# dual_encoder_shield_revC.net
KiCad netlist of a schematic drawn in EAGLE
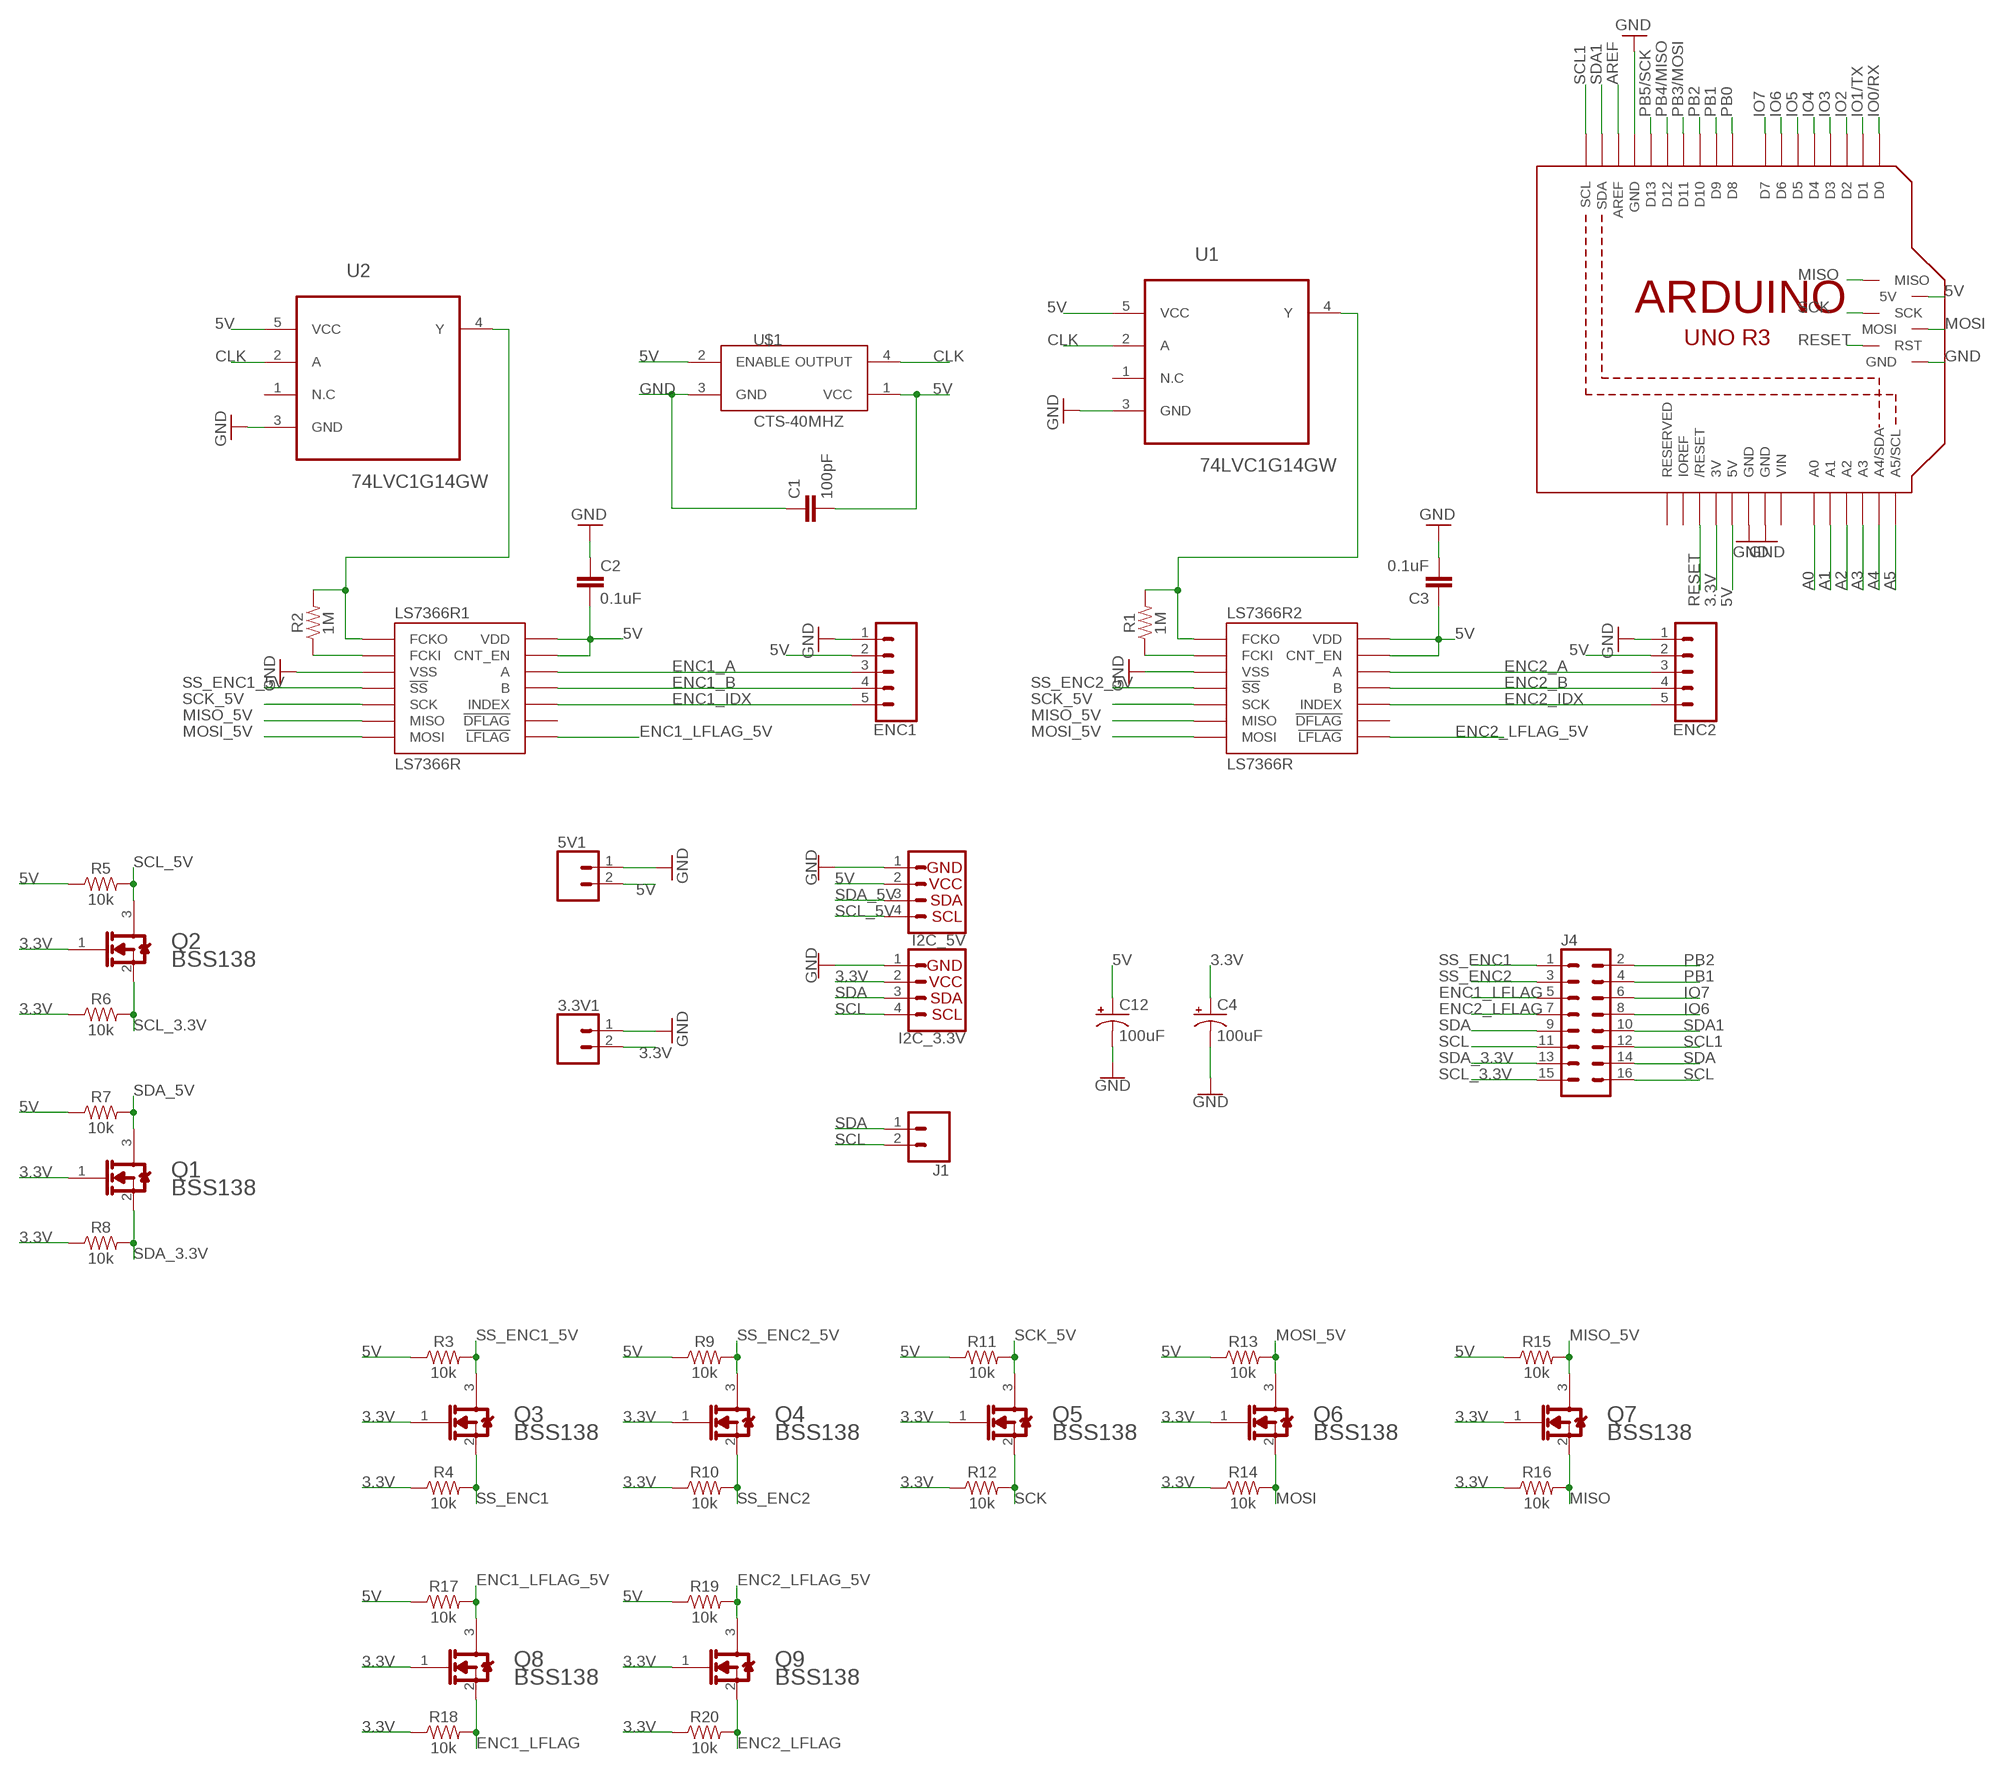
[diagram p0: schematic, sheet 1]

(export (version "E")
  (design (tool "Eeschema 10.0.6"))
  (components
    (comp (ref "3.3V1")
      (value "CONN_02-JST-2MM-SMT")
      (footprint "eagle-import:JST-2-SMD")
      (libsource (lib "eagle-import") (part "CONN_02-JST-2MM-SMT"))
    )
    (comp (ref "5V1")
      (value "CONN_02-JST-2MM-SMT")
      (footprint "eagle-import:JST-2-SMD")
      (libsource (lib "eagle-import") (part "CONN_02-JST-2MM-SMT"))
    )
    (comp (ref "C1")
      (value "100pF")
      (footprint "eagle-import:0603")
      (libsource (lib "eagle-import") (part "100PF-0603-50V-5%"))
    )
    (comp (ref "C2")
      (value "0.1uF")
      (footprint "eagle-import:0603")
      (libsource (lib "eagle-import") (part "0.1UF-0603-25V-5%"))
    )
    (comp (ref "C3")
      (value "0.1uF")
      (footprint "eagle-import:0603")
      (libsource (lib "eagle-import") (part "0.1UF-0603-25V-5%"))
    )
    (comp (ref "C4")
      (value "100uF")
      (footprint "eagle-import:PANASONIC_D")
      (libsource (lib "eagle-import") (part "100UF-POLAR-25V-20%(ELEC)"))
    )
    (comp (ref "C12")
      (value "100uF")
      (footprint "eagle-import:PANASONIC_D")
      (libsource (lib "eagle-import") (part "100UF-POLAR-25V-20%(ELEC)"))
    )
    (comp (ref "ENC1")
      (value "CONN_05")
      (footprint "eagle-import:1X05")
      (libsource (lib "eagle-import") (part "CONN_05"))
    )
    (comp (ref "ENC2")
      (value "CONN_05")
      (footprint "eagle-import:1X05")
      (libsource (lib "eagle-import") (part "CONN_05"))
    )
    (comp (ref "I2C_3.3V")
      (value "QWIIC_CONNECTORJS-1MM")
      (footprint "eagle-import:JST04_1MM_RA")
      (libsource (lib "eagle-import") (part "QWIIC_CONNECTORJS-1MM"))
    )
    (comp (ref "I2C_5V")
      (value "QWIIC_CONNECTORJS-1MM")
      (footprint "eagle-import:JST04_1MM_RA")
      (libsource (lib "eagle-import") (part "QWIIC_CONNECTORJS-1MM"))
    )
    (comp (ref "J1")
      (value "CONN_02")
      (footprint "eagle-import:1X02")
      (libsource (lib "eagle-import") (part "CONN_02"))
    )
    (comp (ref "J4")
      (value "CONN_08X2")
      (footprint "eagle-import:2X8")
      (libsource (lib "eagle-import") (part "CONN_08X2"))
    )
    (comp (ref "LS7366R1")
      (value "LS7366R")
      (footprint "eagle-import:SOIC14")
      (fields (field (name "MF") "LSI"))
      (libsource (lib "eagle-import") (part "LS7366R"))
    )
    (comp (ref "LS7366R2")
      (value "LS7366R")
      (footprint "eagle-import:SOIC14")
      (fields (field (name "MF") "LSI"))
      (libsource (lib "eagle-import") (part "LS7366R"))
    )
    (comp (ref "M1")
      (value "ARDUINO_R3_ICSP")
      (footprint "eagle-import:ARDUINOR3_ICSP")
      (libsource (lib "eagle-import") (part "ARDUINO_R3_ICSP"))
    )
    (comp (ref "Q1")
      (value "ON_SEMI_BSS138ON_SEMI_BSS138_0_0")
      (footprint "eagle-import:ON_SEMI_BSS138_0")
      (fields
        (field (name "DIGIKEY_PART_NUMBER") "BSS138CT-ND")
        (field (name "MF") "ON Semi")
        (field (name "MOUSER_PART_NUMBER") "512-BSS138")
      )
      (libsource (lib "eagle-import") (part "ON_SEMI_BSS138ON_SEMI_BSS138_0_0"))
    )
    (comp (ref "Q2")
      (value "ON_SEMI_BSS138ON_SEMI_BSS138_0_0")
      (footprint "eagle-import:ON_SEMI_BSS138_0")
      (fields
        (field (name "DIGIKEY_PART_NUMBER") "BSS138CT-ND")
        (field (name "MF") "ON Semi")
        (field (name "MOUSER_PART_NUMBER") "512-BSS138")
      )
      (libsource (lib "eagle-import") (part "ON_SEMI_BSS138ON_SEMI_BSS138_0_0"))
    )
    (comp (ref "Q3")
      (value "ON_SEMI_BSS138ON_SEMI_BSS138_0_0")
      (footprint "eagle-import:ON_SEMI_BSS138_0")
      (fields
        (field (name "DIGIKEY_PART_NUMBER") "BSS138CT-ND")
        (field (name "MF") "ON Semi")
        (field (name "MOUSER_PART_NUMBER") "512-BSS138")
      )
      (libsource (lib "eagle-import") (part "ON_SEMI_BSS138ON_SEMI_BSS138_0_0"))
    )
    (comp (ref "Q4")
      (value "ON_SEMI_BSS138ON_SEMI_BSS138_0_0")
      (footprint "eagle-import:ON_SEMI_BSS138_0")
      (fields
        (field (name "DIGIKEY_PART_NUMBER") "BSS138CT-ND")
        (field (name "MF") "ON Semi")
        (field (name "MOUSER_PART_NUMBER") "512-BSS138")
      )
      (libsource (lib "eagle-import") (part "ON_SEMI_BSS138ON_SEMI_BSS138_0_0"))
    )
    (comp (ref "Q5")
      (value "ON_SEMI_BSS138ON_SEMI_BSS138_0_0")
      (footprint "eagle-import:ON_SEMI_BSS138_0")
      (fields
        (field (name "DIGIKEY_PART_NUMBER") "BSS138CT-ND")
        (field (name "MF") "ON Semi")
        (field (name "MOUSER_PART_NUMBER") "512-BSS138")
      )
      (libsource (lib "eagle-import") (part "ON_SEMI_BSS138ON_SEMI_BSS138_0_0"))
    )
    (comp (ref "Q6")
      (value "ON_SEMI_BSS138ON_SEMI_BSS138_0_0")
      (footprint "eagle-import:ON_SEMI_BSS138_0")
      (fields
        (field (name "DIGIKEY_PART_NUMBER") "BSS138CT-ND")
        (field (name "MF") "ON Semi")
        (field (name "MOUSER_PART_NUMBER") "512-BSS138")
      )
      (libsource (lib "eagle-import") (part "ON_SEMI_BSS138ON_SEMI_BSS138_0_0"))
    )
    (comp (ref "Q7")
      (value "ON_SEMI_BSS138ON_SEMI_BSS138_0_0")
      (footprint "eagle-import:ON_SEMI_BSS138_0")
      (fields
        (field (name "DIGIKEY_PART_NUMBER") "BSS138CT-ND")
        (field (name "MF") "ON Semi")
        (field (name "MOUSER_PART_NUMBER") "512-BSS138")
      )
      (libsource (lib "eagle-import") (part "ON_SEMI_BSS138ON_SEMI_BSS138_0_0"))
    )
    (comp (ref "Q8")
      (value "ON_SEMI_BSS138ON_SEMI_BSS138_0_0")
      (footprint "eagle-import:ON_SEMI_BSS138_0")
      (fields
        (field (name "DIGIKEY_PART_NUMBER") "BSS138CT-ND")
        (field (name "MF") "ON Semi")
        (field (name "MOUSER_PART_NUMBER") "512-BSS138")
      )
      (libsource (lib "eagle-import") (part "ON_SEMI_BSS138ON_SEMI_BSS138_0_0"))
    )
    (comp (ref "Q9")
      (value "ON_SEMI_BSS138ON_SEMI_BSS138_0_0")
      (footprint "eagle-import:ON_SEMI_BSS138_0")
      (fields
        (field (name "DIGIKEY_PART_NUMBER") "BSS138CT-ND")
        (field (name "MF") "ON Semi")
        (field (name "MOUSER_PART_NUMBER") "512-BSS138")
      )
      (libsource (lib "eagle-import") (part "ON_SEMI_BSS138ON_SEMI_BSS138_0_0"))
    )
    (comp (ref "R1")
      (value "1M")
      (footprint "eagle-import:0603")
      (libsource (lib "eagle-import") (part "1MOHM-0603-1/4W-5%"))
    )
    (comp (ref "R2")
      (value "1M")
      (footprint "eagle-import:0603")
      (libsource (lib "eagle-import") (part "1MOHM-0603-1/4W-5%"))
    )
    (comp (ref "R3")
      (value "10k")
      (footprint "eagle-import:0603")
      (libsource (lib "eagle-import") (part "10KOHM-0603-1/10W-1%"))
    )
    (comp (ref "R4")
      (value "10k")
      (footprint "eagle-import:0603")
      (libsource (lib "eagle-import") (part "10KOHM-0603-1/10W-1%"))
    )
    (comp (ref "R5")
      (value "10k")
      (footprint "eagle-import:0603")
      (libsource (lib "eagle-import") (part "10KOHM-0603-1/10W-1%"))
    )
    (comp (ref "R6")
      (value "10k")
      (footprint "eagle-import:0603")
      (libsource (lib "eagle-import") (part "10KOHM-0603-1/10W-1%"))
    )
    (comp (ref "R7")
      (value "10k")
      (footprint "eagle-import:0603")
      (libsource (lib "eagle-import") (part "10KOHM-0603-1/10W-1%"))
    )
    (comp (ref "R8")
      (value "10k")
      (footprint "eagle-import:0603")
      (libsource (lib "eagle-import") (part "10KOHM-0603-1/10W-1%"))
    )
    (comp (ref "R9")
      (value "10k")
      (footprint "eagle-import:0603")
      (libsource (lib "eagle-import") (part "10KOHM-0603-1/10W-1%"))
    )
    (comp (ref "R10")
      (value "10k")
      (footprint "eagle-import:0603")
      (libsource (lib "eagle-import") (part "10KOHM-0603-1/10W-1%"))
    )
    (comp (ref "R11")
      (value "10k")
      (footprint "eagle-import:0603")
      (libsource (lib "eagle-import") (part "10KOHM-0603-1/10W-1%"))
    )
    (comp (ref "R12")
      (value "10k")
      (footprint "eagle-import:0603")
      (libsource (lib "eagle-import") (part "10KOHM-0603-1/10W-1%"))
    )
    (comp (ref "R13")
      (value "10k")
      (footprint "eagle-import:0603")
      (libsource (lib "eagle-import") (part "10KOHM-0603-1/10W-1%"))
    )
    (comp (ref "R14")
      (value "10k")
      (footprint "eagle-import:0603")
      (libsource (lib "eagle-import") (part "10KOHM-0603-1/10W-1%"))
    )
    (comp (ref "R15")
      (value "10k")
      (footprint "eagle-import:0603")
      (libsource (lib "eagle-import") (part "10KOHM-0603-1/10W-1%"))
    )
    (comp (ref "R16")
      (value "10k")
      (footprint "eagle-import:0603")
      (libsource (lib "eagle-import") (part "10KOHM-0603-1/10W-1%"))
    )
    (comp (ref "R17")
      (value "10k")
      (footprint "eagle-import:0603")
      (libsource (lib "eagle-import") (part "10KOHM-0603-1/10W-1%"))
    )
    (comp (ref "R18")
      (value "10k")
      (footprint "eagle-import:0603")
      (libsource (lib "eagle-import") (part "10KOHM-0603-1/10W-1%"))
    )
    (comp (ref "R19")
      (value "10k")
      (footprint "eagle-import:0603")
      (libsource (lib "eagle-import") (part "10KOHM-0603-1/10W-1%"))
    )
    (comp (ref "R20")
      (value "10k")
      (footprint "eagle-import:0603")
      (libsource (lib "eagle-import") (part "10KOHM-0603-1/10W-1%"))
    )
    (comp (ref "U$1")
      (value "CTS-40MHZ")
      (footprint "eagle-import:SOIC254P1016X440-4N")
      (libsource (lib "eagle-import") (part "CTS-40MHZ"))
    )
    (comp (ref "U1")
      (value "74LVC1G14GW")
      (footprint "eagle-import:SOT65P210X110-5N")
      (fields (field (name "MF") "NXP Semiconductors"))
      (libsource (lib "eagle-import") (part "74LVC1G14GW"))
    )
    (comp (ref "U2")
      (value "74LVC1G14GW")
      (footprint "eagle-import:SOT65P210X110-5N")
      (fields (field (name "MF") "NXP Semiconductors"))
      (libsource (lib "eagle-import") (part "74LVC1G14GW"))
    )
  )
  (nets
    (net (code "1") (name "/3.3V") (class "Default")
      (node (ref "3.3V1") (pin "2") (pinfunction "1_2") (pintype "passive"))
      (node (ref "C4") (pin "+") (pinfunction "+_+") (pintype "passive"))
      (node (ref "I2C_3.3V") (pin "2") (pinfunction "2_2") (pintype "power_in"))
      (node (ref "M1") (pin "3V") (pinfunction "3V_3V") (pintype "power_in"))
      (node (ref "Q1") (pin "1") (pinfunction "G_1") (pintype "bidirectional"))
      (node (ref "Q2") (pin "1") (pinfunction "G_1") (pintype "bidirectional"))
      (node (ref "Q3") (pin "1") (pinfunction "G_1") (pintype "bidirectional"))
      (node (ref "Q4") (pin "1") (pinfunction "G_1") (pintype "bidirectional"))
      (node (ref "Q5") (pin "1") (pinfunction "G_1") (pintype "bidirectional"))
      (node (ref "Q6") (pin "1") (pinfunction "G_1") (pintype "bidirectional"))
      (node (ref "Q7") (pin "1") (pinfunction "G_1") (pintype "bidirectional"))
      (node (ref "Q8") (pin "1") (pinfunction "G_1") (pintype "bidirectional"))
      (node (ref "Q9") (pin "1") (pinfunction "G_1") (pintype "bidirectional"))
      (node (ref "R10") (pin "1") (pinfunction "1_1") (pintype "passive"))
      (node (ref "R12") (pin "1") (pinfunction "1_1") (pintype "passive"))
      (node (ref "R14") (pin "1") (pinfunction "1_1") (pintype "passive"))
      (node (ref "R16") (pin "1") (pinfunction "1_1") (pintype "passive"))
      (node (ref "R18") (pin "1") (pinfunction "1_1") (pintype "passive"))
      (node (ref "R20") (pin "1") (pinfunction "1_1") (pintype "passive"))
      (node (ref "R4") (pin "1") (pinfunction "1_1") (pintype "passive"))
      (node (ref "R6") (pin "1") (pinfunction "1_1") (pintype "passive"))
      (node (ref "R8") (pin "1") (pinfunction "1_1") (pintype "passive"))
    )
    (net (code "2") (name "/5V") (class "Default")
      (node (ref "5V1") (pin "2") (pinfunction "1_2") (pintype "passive"))
      (node (ref "C1") (pin "2") (pinfunction "2_2") (pintype "passive"))
      (node (ref "C12") (pin "+") (pinfunction "+_+") (pintype "passive"))
      (node (ref "C2") (pin "2") (pinfunction "2_2") (pintype "passive"))
      (node (ref "C3") (pin "1") (pinfunction "1_1") (pintype "passive"))
      (node (ref "ENC1") (pin "2") (pinfunction "2_2") (pintype "passive"))
      (node (ref "ENC2") (pin "2") (pinfunction "2_2") (pintype "passive"))
      (node (ref "I2C_5V") (pin "2") (pinfunction "2_2") (pintype "power_in"))
      (node (ref "LS7366R1") (pin "13") (pinfunction "CNT_EN_13") (pintype "bidirectional"))
      (node (ref "LS7366R1") (pin "14") (pinfunction "VDD_14") (pintype "bidirectional"))
      (node (ref "LS7366R2") (pin "13") (pinfunction "CNT_EN_13") (pintype "bidirectional"))
      (node (ref "LS7366R2") (pin "14") (pinfunction "VDD_14") (pintype "bidirectional"))
      (node (ref "M1") (pin "5V") (pinfunction "5V_5V") (pintype "power_in"))
      (node (ref "M1") (pin "5V_ICSP") (pinfunction "5V_5V_ICSP") (pintype "passive"))
      (node (ref "R11") (pin "1") (pinfunction "1_1") (pintype "passive"))
      (node (ref "R13") (pin "1") (pinfunction "1_1") (pintype "passive"))
      (node (ref "R15") (pin "1") (pinfunction "1_1") (pintype "passive"))
      (node (ref "R17") (pin "1") (pinfunction "1_1") (pintype "passive"))
      (node (ref "R19") (pin "1") (pinfunction "1_1") (pintype "passive"))
      (node (ref "R3") (pin "1") (pinfunction "1_1") (pintype "passive"))
      (node (ref "R5") (pin "1") (pinfunction "1_1") (pintype "passive"))
      (node (ref "R7") (pin "1") (pinfunction "1_1") (pintype "passive"))
      (node (ref "R9") (pin "1") (pinfunction "1_1") (pintype "passive"))
      (node (ref "U$1") (pin "1") (pinfunction "VCC_1") (pintype "bidirectional"))
      (node (ref "U$1") (pin "2") (pinfunction "ENABLE_2") (pintype "bidirectional"))
      (node (ref "U1") (pin "5") (pinfunction "VCC_5") (pintype "power_in"))
      (node (ref "U2") (pin "5") (pinfunction "VCC_5") (pintype "power_in"))
    )
    (net (code "3") (name "/A0") (class "Default")
      (node (ref "M1") (pin "A0") (pinfunction "A0_A0") (pintype "bidirectional"))
    )
    (net (code "4") (name "/A1") (class "Default")
      (node (ref "M1") (pin "A1") (pinfunction "A1_A1") (pintype "bidirectional"))
    )
    (net (code "5") (name "/A2") (class "Default")
      (node (ref "M1") (pin "A2") (pinfunction "A2_A2") (pintype "bidirectional"))
    )
    (net (code "6") (name "/A3") (class "Default")
      (node (ref "M1") (pin "A3") (pinfunction "A3_A3") (pintype "bidirectional"))
    )
    (net (code "7") (name "/A4") (class "Default")
      (node (ref "M1") (pin "A4") (pinfunction "A4/SDA_A4") (pintype "bidirectional"))
    )
    (net (code "8") (name "/A5") (class "Default")
      (node (ref "M1") (pin "A5") (pinfunction "A5/SCL_A5") (pintype "bidirectional"))
    )
    (net (code "9") (name "/AREF") (class "Default")
      (node (ref "M1") (pin "AREF") (pinfunction "AREF_AREF") (pintype "bidirectional"))
    )
    (net (code "10") (name "/CLK") (class "Default")
      (node (ref "U$1") (pin "4") (pinfunction "OUTPUT_4") (pintype "bidirectional"))
      (node (ref "U1") (pin "2") (pinfunction "A_2") (pintype "input"))
      (node (ref "U2") (pin "2") (pinfunction "A_2") (pintype "input"))
    )
    (net (code "11") (name "/ENC1_A") (class "Default")
      (node (ref "ENC1") (pin "3") (pinfunction "3_3") (pintype "passive"))
      (node (ref "LS7366R1") (pin "12") (pinfunction "A_12") (pintype "bidirectional"))
    )
    (net (code "12") (name "/ENC1_B") (class "Default")
      (node (ref "ENC1") (pin "4") (pinfunction "4_4") (pintype "passive"))
      (node (ref "LS7366R1") (pin "11") (pinfunction "B_11") (pintype "bidirectional"))
    )
    (net (code "13") (name "/ENC1_IDX") (class "Default")
      (node (ref "ENC1") (pin "5") (pinfunction "5_5") (pintype "passive"))
      (node (ref "LS7366R1") (pin "10") (pinfunction "INDEX_10") (pintype "bidirectional"))
    )
    (net (code "14") (name "/ENC1_LFLAG") (class "Default")
      (node (ref "J4") (pin "5") (pinfunction "5_5") (pintype "passive"))
      (node (ref "Q8") (pin "2") (pinfunction "S_2") (pintype "bidirectional"))
      (node (ref "R18") (pin "2") (pinfunction "2_2") (pintype "passive"))
    )
    (net (code "15") (name "/ENC1_LFLAG_5V") (class "Default")
      (node (ref "LS7366R1") (pin "8") (pinfunction "~{LFLAG}_8") (pintype "bidirectional"))
      (node (ref "Q8") (pin "3") (pinfunction "D_3") (pintype "bidirectional"))
      (node (ref "R17") (pin "2") (pinfunction "2_2") (pintype "passive"))
    )
    (net (code "16") (name "/ENC2_A") (class "Default")
      (node (ref "ENC2") (pin "3") (pinfunction "3_3") (pintype "passive"))
      (node (ref "LS7366R2") (pin "12") (pinfunction "A_12") (pintype "bidirectional"))
    )
    (net (code "17") (name "/ENC2_B") (class "Default")
      (node (ref "ENC2") (pin "4") (pinfunction "4_4") (pintype "passive"))
      (node (ref "LS7366R2") (pin "11") (pinfunction "B_11") (pintype "bidirectional"))
    )
    (net (code "18") (name "/ENC2_IDX") (class "Default")
      (node (ref "ENC2") (pin "5") (pinfunction "5_5") (pintype "passive"))
      (node (ref "LS7366R2") (pin "10") (pinfunction "INDEX_10") (pintype "bidirectional"))
    )
    (net (code "19") (name "/ENC2_LFLAG") (class "Default")
      (node (ref "J4") (pin "7") (pinfunction "7_7") (pintype "passive"))
      (node (ref "Q9") (pin "2") (pinfunction "S_2") (pintype "bidirectional"))
      (node (ref "R20") (pin "2") (pinfunction "2_2") (pintype "passive"))
    )
    (net (code "20") (name "/ENC2_LFLAG_5V") (class "Default")
      (node (ref "LS7366R2") (pin "8") (pinfunction "~{LFLAG}_8") (pintype "bidirectional"))
      (node (ref "Q9") (pin "3") (pinfunction "D_3") (pintype "bidirectional"))
      (node (ref "R19") (pin "2") (pinfunction "2_2") (pintype "passive"))
    )
    (net (code "21") (name "/IO0{slash}RX") (class "Default")
      (node (ref "M1") (pin "D0") (pinfunction "D0_D0") (pintype "bidirectional"))
    )
    (net (code "22") (name "/IO1{slash}TX") (class "Default")
      (node (ref "M1") (pin "D1") (pinfunction "D1_D1") (pintype "bidirectional"))
    )
    (net (code "23") (name "/IO2") (class "Default")
      (node (ref "M1") (pin "D2") (pinfunction "D2_D2") (pintype "bidirectional"))
    )
    (net (code "24") (name "/IO3") (class "Default")
      (node (ref "M1") (pin "D3") (pinfunction "D3_D3") (pintype "bidirectional"))
    )
    (net (code "25") (name "/IO4") (class "Default")
      (node (ref "M1") (pin "D4") (pinfunction "D4_D4") (pintype "bidirectional"))
    )
    (net (code "26") (name "/IO5") (class "Default")
      (node (ref "M1") (pin "D5") (pinfunction "D5_D5") (pintype "bidirectional"))
    )
    (net (code "27") (name "/IO6") (class "Default")
      (node (ref "J4") (pin "8") (pinfunction "8_8") (pintype "passive"))
      (node (ref "M1") (pin "D6") (pinfunction "D6_D6") (pintype "bidirectional"))
    )
    (net (code "28") (name "/IO7") (class "Default")
      (node (ref "J4") (pin "6") (pinfunction "6_6") (pintype "passive"))
      (node (ref "M1") (pin "D7") (pinfunction "D7_D7") (pintype "bidirectional"))
    )
    (net (code "29") (name "/MISO") (class "Default")
      (node (ref "M1") (pin "MISO") (pinfunction "MISO_MISO") (pintype "passive"))
      (node (ref "Q7") (pin "2") (pinfunction "S_2") (pintype "bidirectional"))
      (node (ref "R16") (pin "2") (pinfunction "2_2") (pintype "passive"))
    )
    (net (code "30") (name "/MISO_5V") (class "Default")
      (node (ref "LS7366R1") (pin "6") (pinfunction "MISO_6") (pintype "bidirectional"))
      (node (ref "LS7366R2") (pin "6") (pinfunction "MISO_6") (pintype "bidirectional"))
      (node (ref "Q7") (pin "3") (pinfunction "D_3") (pintype "bidirectional"))
      (node (ref "R15") (pin "2") (pinfunction "2_2") (pintype "passive"))
    )
    (net (code "31") (name "/MOSI") (class "Default")
      (node (ref "M1") (pin "MOSI") (pinfunction "MOSI_MOSI") (pintype "passive"))
      (node (ref "Q6") (pin "2") (pinfunction "S_2") (pintype "bidirectional"))
      (node (ref "R14") (pin "2") (pinfunction "2_2") (pintype "passive"))
    )
    (net (code "32") (name "/MOSI_5V") (class "Default")
      (node (ref "LS7366R1") (pin "7") (pinfunction "MOSI_7") (pintype "bidirectional"))
      (node (ref "LS7366R2") (pin "7") (pinfunction "MOSI_7") (pintype "bidirectional"))
      (node (ref "Q6") (pin "3") (pinfunction "D_3") (pintype "bidirectional"))
      (node (ref "R13") (pin "2") (pinfunction "2_2") (pintype "passive"))
    )
    (net (code "33") (name "/PB0") (class "Default")
      (node (ref "M1") (pin "D8") (pinfunction "D8_D8") (pintype "bidirectional"))
    )
    (net (code "34") (name "/PB1") (class "Default")
      (node (ref "J4") (pin "4") (pinfunction "4_4") (pintype "passive"))
      (node (ref "M1") (pin "D9") (pinfunction "D9_D9") (pintype "bidirectional"))
    )
    (net (code "35") (name "/PB2") (class "Default")
      (node (ref "J4") (pin "2") (pinfunction "2_2") (pintype "passive"))
      (node (ref "M1") (pin "D10") (pinfunction "D10_D10") (pintype "bidirectional"))
    )
    (net (code "36") (name "/PB3{slash}MOSI") (class "Default")
      (node (ref "M1") (pin "D11") (pinfunction "D11_D11") (pintype "bidirectional"))
    )
    (net (code "37") (name "/PB4{slash}MISO") (class "Default")
      (node (ref "M1") (pin "D12") (pinfunction "D12_D12") (pintype "bidirectional"))
    )
    (net (code "38") (name "/PB5{slash}SCK") (class "Default")
      (node (ref "M1") (pin "D13") (pinfunction "D13_D13") (pintype "bidirectional"))
    )
    (net (code "39") (name "/RESET") (class "Default")
      (node (ref "M1") (pin "RESET") (pinfunction "/RESET_RESET") (pintype "bidirectional"))
      (node (ref "M1") (pin "RESET_ICSP") (pinfunction "RST_RESET_ICSP") (pintype "passive"))
    )
    (net (code "40") (name "/SCK") (class "Default")
      (node (ref "M1") (pin "SCK") (pinfunction "SCK_SCK") (pintype "passive"))
      (node (ref "Q5") (pin "2") (pinfunction "S_2") (pintype "bidirectional"))
      (node (ref "R12") (pin "2") (pinfunction "2_2") (pintype "passive"))
    )
    (net (code "41") (name "/SCK_5V") (class "Default")
      (node (ref "LS7366R1") (pin "5") (pinfunction "SCK_5") (pintype "bidirectional"))
      (node (ref "LS7366R2") (pin "5") (pinfunction "SCK_5") (pintype "bidirectional"))
      (node (ref "Q5") (pin "3") (pinfunction "D_3") (pintype "bidirectional"))
      (node (ref "R11") (pin "2") (pinfunction "2_2") (pintype "passive"))
    )
    (net (code "42") (name "/SCL") (class "Default")
      (node (ref "I2C_3.3V") (pin "4") (pinfunction "4_4") (pintype "passive"))
      (node (ref "J1") (pin "2") (pinfunction "2_2") (pintype "passive"))
      (node (ref "J4") (pin "11") (pinfunction "11_11") (pintype "passive"))
      (node (ref "J4") (pin "16") (pinfunction "16_16") (pintype "passive"))
    )
    (net (code "43") (name "/SCL1") (class "Default")
      (node (ref "J4") (pin "12") (pinfunction "12_12") (pintype "passive"))
      (node (ref "M1") (pin "SCL") (pinfunction "SCL_SCL") (pintype "bidirectional"))
    )
    (net (code "44") (name "/SCL_3.3V") (class "Default")
      (node (ref "J4") (pin "15") (pinfunction "15_15") (pintype "passive"))
      (node (ref "Q2") (pin "2") (pinfunction "S_2") (pintype "bidirectional"))
      (node (ref "R6") (pin "2") (pinfunction "2_2") (pintype "passive"))
    )
    (net (code "45") (name "/SCL_5V") (class "Default")
      (node (ref "I2C_5V") (pin "4") (pinfunction "4_4") (pintype "passive"))
      (node (ref "Q2") (pin "3") (pinfunction "D_3") (pintype "bidirectional"))
      (node (ref "R5") (pin "2") (pinfunction "2_2") (pintype "passive"))
    )
    (net (code "46") (name "/SDA") (class "Default")
      (node (ref "I2C_3.3V") (pin "3") (pinfunction "3_3") (pintype "passive"))
      (node (ref "J1") (pin "1") (pinfunction "1_1") (pintype "passive"))
      (node (ref "J4") (pin "14") (pinfunction "14_14") (pintype "passive"))
      (node (ref "J4") (pin "9") (pinfunction "9_9") (pintype "passive"))
    )
    (net (code "47") (name "/SDA1") (class "Default")
      (node (ref "J4") (pin "10") (pinfunction "10_10") (pintype "passive"))
      (node (ref "M1") (pin "SDA") (pinfunction "SDA_SDA") (pintype "bidirectional"))
    )
    (net (code "48") (name "/SDA_3.3V") (class "Default")
      (node (ref "J4") (pin "13") (pinfunction "13_13") (pintype "passive"))
      (node (ref "Q1") (pin "2") (pinfunction "S_2") (pintype "bidirectional"))
      (node (ref "R8") (pin "2") (pinfunction "2_2") (pintype "passive"))
    )
    (net (code "49") (name "/SDA_5V") (class "Default")
      (node (ref "I2C_5V") (pin "3") (pinfunction "3_3") (pintype "passive"))
      (node (ref "Q1") (pin "3") (pinfunction "D_3") (pintype "bidirectional"))
      (node (ref "R7") (pin "2") (pinfunction "2_2") (pintype "passive"))
    )
    (net (code "50") (name "/SS_ENC1") (class "Default")
      (node (ref "J4") (pin "1") (pinfunction "1_1") (pintype "passive"))
      (node (ref "Q3") (pin "2") (pinfunction "S_2") (pintype "bidirectional"))
      (node (ref "R4") (pin "2") (pinfunction "2_2") (pintype "passive"))
    )
    (net (code "51") (name "/SS_ENC1_5V") (class "Default")
      (node (ref "LS7366R1") (pin "4") (pinfunction "~{SS}_4") (pintype "bidirectional"))
      (node (ref "Q3") (pin "3") (pinfunction "D_3") (pintype "bidirectional"))
      (node (ref "R3") (pin "2") (pinfunction "2_2") (pintype "passive"))
    )
    (net (code "52") (name "/SS_ENC2") (class "Default")
      (node (ref "J4") (pin "3") (pinfunction "3_3") (pintype "passive"))
      (node (ref "Q4") (pin "2") (pinfunction "S_2") (pintype "bidirectional"))
      (node (ref "R10") (pin "2") (pinfunction "2_2") (pintype "passive"))
    )
    (net (code "53") (name "/SS_ENC2_5V") (class "Default")
      (node (ref "LS7366R2") (pin "4") (pinfunction "~{SS}_4") (pintype "bidirectional"))
      (node (ref "Q4") (pin "3") (pinfunction "D_3") (pintype "bidirectional"))
      (node (ref "R9") (pin "2") (pinfunction "2_2") (pintype "passive"))
    )
    (net (code "54") (name "/VIN") (class "Default")
      (node (ref "M1") (pin "VIN") (pinfunction "VIN_VIN") (pintype "power_in"))
    )
    (net (code "55") (name "GND") (class "Default")
      (node (ref "3.3V1") (pin "1") (pinfunction "2_1") (pintype "passive"))
      (node (ref "5V1") (pin "1") (pinfunction "2_1") (pintype "passive"))
      (node (ref "C1") (pin "1") (pinfunction "1_1") (pintype "passive"))
      (node (ref "C12") (pin "-") (pinfunction "-_-") (pintype "passive"))
      (node (ref "C2") (pin "1") (pinfunction "1_1") (pintype "passive"))
      (node (ref "C3") (pin "2") (pinfunction "2_2") (pintype "passive"))
      (node (ref "C4") (pin "-") (pinfunction "-_-") (pintype "passive"))
      (node (ref "ENC1") (pin "1") (pinfunction "1_1") (pintype "passive"))
      (node (ref "ENC2") (pin "1") (pinfunction "1_1") (pintype "passive"))
      (node (ref "I2C_3.3V") (pin "1") (pinfunction "1_1") (pintype "power_in"))
      (node (ref "I2C_5V") (pin "1") (pinfunction "1_1") (pintype "power_in"))
      (node (ref "LS7366R1") (pin "3") (pinfunction "VSS_3") (pintype "bidirectional"))
      (node (ref "LS7366R2") (pin "3") (pinfunction "VSS_3") (pintype "bidirectional"))
      (node (ref "M1") (pin "GND") (pinfunction "GND_GND") (pintype "power_in"))
      (node (ref "M1") (pin "GND@1") (pinfunction "GND_GND@1") (pintype "power_in"))
      (node (ref "M1") (pin "GND@2") (pinfunction "GND_GND@2") (pintype "passive"))
      (node (ref "M1") (pin "GND@3") (pinfunction "GND_GND@3") (pintype "power_in"))
      (node (ref "U$1") (pin "3") (pinfunction "GND_3") (pintype "bidirectional"))
      (node (ref "U1") (pin "3") (pinfunction "GND_3") (pintype "passive"))
      (node (ref "U2") (pin "3") (pinfunction "GND_3") (pintype "passive"))
    )
    (net (code "56") (name "Net-(LS7366R1-FCKI)") (class "Default")
      (node (ref "LS7366R1") (pin "2") (pinfunction "FCKI_2") (pintype "bidirectional"))
      (node (ref "R2") (pin "1") (pinfunction "1_1") (pintype "passive"))
    )
    (net (code "57") (name "Net-(LS7366R1-FCKO)") (class "Default")
      (node (ref "LS7366R1") (pin "1") (pinfunction "FCKO_1") (pintype "bidirectional"))
      (node (ref "R2") (pin "2") (pinfunction "2_2") (pintype "passive"))
      (node (ref "U2") (pin "4") (pinfunction "Y_4") (pintype "output"))
    )
    (net (code "58") (name "Net-(LS7366R2-FCKI)") (class "Default")
      (node (ref "LS7366R2") (pin "2") (pinfunction "FCKI_2") (pintype "bidirectional"))
      (node (ref "R1") (pin "1") (pinfunction "1_1") (pintype "passive"))
    )
    (net (code "59") (name "Net-(LS7366R2-FCKO)") (class "Default")
      (node (ref "LS7366R2") (pin "1") (pinfunction "FCKO_1") (pintype "bidirectional"))
      (node (ref "R1") (pin "2") (pinfunction "2_2") (pintype "passive"))
      (node (ref "U1") (pin "4") (pinfunction "Y_4") (pintype "output"))
    )
    (net (code "60") (name "unconnected-(LS7366R1-~{DFLAG}-Pad9)") (class "Default")
      (node (ref "LS7366R1") (pin "9") (pinfunction "~{DFLAG}_9") (pintype "bidirectional"))
    )
    (net (code "61") (name "unconnected-(LS7366R2-~{DFLAG}-Pad9)") (class "Default")
      (node (ref "LS7366R2") (pin "9") (pinfunction "~{DFLAG}_9") (pintype "bidirectional"))
    )
    (net (code "62") (name "unconnected-(M1-PadIOREF)") (class "Default")
      (node (ref "M1") (pin "IOREF") (pinfunction "IOREF_IOREF") (pintype "output"))
    )
    (net (code "63") (name "unconnected-(M1-PadRESERVED)") (class "Default")
      (node (ref "M1") (pin "RESERVED") (pinfunction "RESERVED_RESERVED") (pintype "no_connect"))
    )
    (net (code "64") (name "unconnected-(U1-N.C-Pad1)") (class "Default")
      (node (ref "U1") (pin "1") (pinfunction "N.C_1") (pintype "no_connect"))
    )
    (net (code "65") (name "unconnected-(U2-N.C-Pad1)") (class "Default")
      (node (ref "U2") (pin "1") (pinfunction "N.C_1") (pintype "no_connect"))
    )
  )
)
